# CargadorDeBaterias.net
KiCad netlist of a schematic drawn in Altium Designer
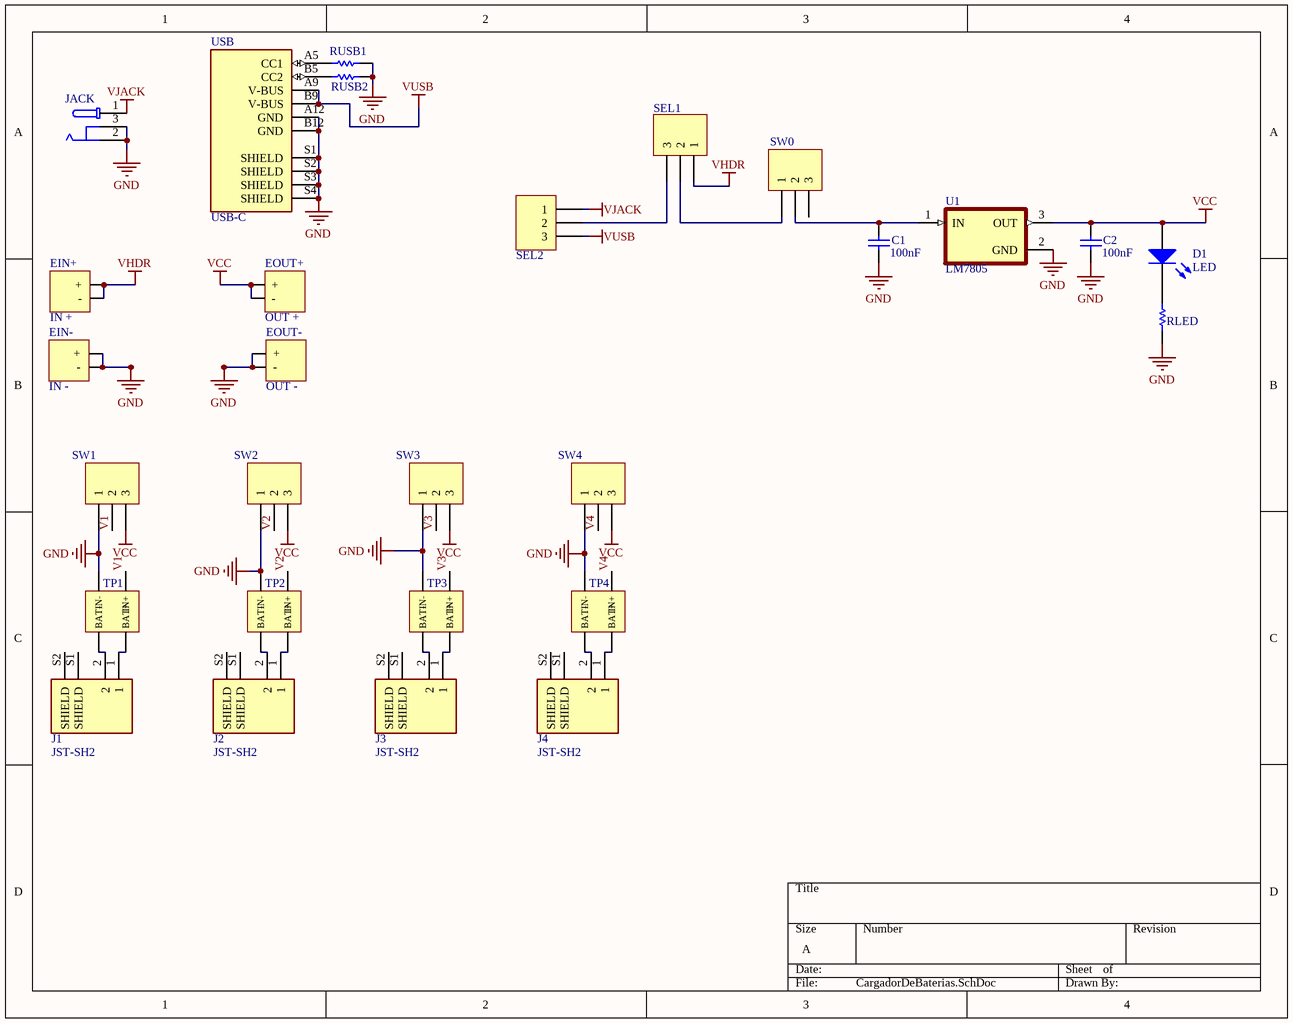
[diagram p0: CargadorDeBaterias.SchDoc]

(export (version "E")
  (design (tool "Eeschema 10.0.6"))
  (components
    (comp (ref "C1")
      (value "100nF")
      (footprint "CAP 0805")
      (description "Capacitor")
      (fields (field (name "Comment") "0805 100nF Capacitor") (field (name "PUBLISHER") "Altium Limited"))
      (libsource (lib "CargadorDeBaterias") (part "Cap"))
    )
    (comp (ref "C2")
      (value "100nF")
      (footprint "CAP 0805")
      (description "Capacitor")
      (fields (field (name "Comment") "0805 100nF Capacitor") (field (name "PUBLISHER") "Altium Limited"))
      (libsource (lib "CargadorDeBaterias") (part "Cap"))
    )
    (comp (ref "D1")
      (value "LED")
      (footprint "LED")
      (fields (field (name "PUBLISHER") "Altium Limited"))
      (libsource (lib "CargadorDeBaterias") (part "LED"))
    )
    (comp (ref "EIN+")
      (value "IN +")
      (footprint "HEADER x2")
      (fields (field (name "PUBLISHER") "Altium Limited"))
      (libsource (lib "") (part "HEADER X2_1"))
    )
    (comp (ref "EIN-")
      (value "IN -")
      (footprint "HEADER x2")
      (fields (field (name "PUBLISHER") "Altium Limited"))
      (libsource (lib "") (part "HEADER X2_1"))
    )
    (comp (ref "EOUT+")
      (value "OUT +")
      (footprint "HEADER x2")
      (fields (field (name "PUBLISHER") "Altium Limited"))
      (libsource (lib "CargadorDeBaterias") (part "HEADER X2"))
    )
    (comp (ref "EOUT-")
      (value "OUT -")
      (footprint "HEADER x2")
      (fields (field (name "PUBLISHER") "Altium Limited"))
      (libsource (lib "CargadorDeBaterias") (part "HEADER X2"))
    )
    (comp (ref "J1")
      (value "JST-SH2")
      (footprint "JST-SH2")
      (fields (field (name "MP") "BM02B-SRSS-TB(LF)(SN)"))
      (libsource (lib "CargadorDeBaterias") (part "JST-SH2"))
    )
    (comp (ref "J2")
      (value "JST-SH2")
      (footprint "JST-SH2")
      (fields (field (name "MP") "BM02B-SRSS-TB(LF)(SN)"))
      (libsource (lib "CargadorDeBaterias") (part "JST-SH2"))
    )
    (comp (ref "J3")
      (value "JST-SH2")
      (footprint "JST-SH2")
      (fields (field (name "MP") "BM02B-SRSS-TB(LF)(SN)"))
      (libsource (lib "CargadorDeBaterias") (part "JST-SH2"))
    )
    (comp (ref "J4")
      (value "JST-SH2")
      (footprint "JST-SH2")
      (fields (field (name "MP") "BM02B-SRSS-TB(LF)(SN)"))
      (libsource (lib "CargadorDeBaterias") (part "JST-SH2"))
    )
    (comp (ref "JACK")
      (value "JACK 5MM")
      (footprint "JACK 5MM")
      (fields (field (name "MF") "MPD") (field (name "MP") "EJ508A"))
      (libsource (lib "CargadorDeBaterias") (part "JACK 5MM"))
    )
    (comp (ref "RLED")
      (value "220ohm 0805 resistor")
      (footprint "RES 0805")
      (fields (field (name "PUBLISHER") "Altium Limited"))
      (libsource (lib "CargadorDeBaterias") (part "RESISTOR 1/4W"))
    )
    (comp (ref "RUSB1")
      (value "5,1Kohm 0805 resistor")
      (footprint "RES 0805")
      (fields (field (name "PUBLISHER") "Altium Limited"))
      (libsource (lib "CargadorDeBaterias") (part "RESISTOR 1/4W"))
    )
    (comp (ref "RUSB2")
      (value "5,1Kohm 0805 resistor")
      (footprint "RES 0805")
      (fields (field (name "PUBLISHER") "Altium Limited"))
      (libsource (lib "CargadorDeBaterias") (part "RESISTOR 1/4W"))
    )
    (comp (ref "SEL1")
      (value "~")
      (footprint "SWITCH PALANCA")
      (fields (field (name "PUBLISHER") "Altium Limited"))
      (libsource (lib "") (part "SLIDE SWITCH_2"))
    )
    (comp (ref "SEL2")
      (value "~")
      (footprint "SWITCH PALANCA")
      (fields (field (name "PUBLISHER") "Altium Limited"))
      (libsource (lib "") (part "SLIDE SWITCH_1"))
    )
    (comp (ref "SW0")
      (value "SLIDE SWITCH")
      (footprint "SWITCH PALANCA")
      (fields (field (name "PUBLISHER") "Altium Limited"))
      (libsource (lib "CargadorDeBaterias") (part "SLIDE SWITCH"))
    )
    (comp (ref "SW1")
      (value "~")
      (footprint "SWITCH PALANCA")
      (fields (field (name "PUBLISHER") "Altium Limited"))
      (libsource (lib "librerias (2)") (part "SLIDE SWITCH"))
    )
    (comp (ref "SW2")
      (value "~")
      (footprint "SWITCH PALANCA")
      (fields (field (name "PUBLISHER") "Altium Limited"))
      (libsource (lib "librerias (2)") (part "SLIDE SWITCH"))
    )
    (comp (ref "SW3")
      (value "~")
      (footprint "SWITCH PALANCA")
      (fields (field (name "PUBLISHER") "Altium Limited"))
      (libsource (lib "librerias (2)") (part "SLIDE SWITCH"))
    )
    (comp (ref "SW4")
      (value "~")
      (footprint "SWITCH PALANCA")
      (fields (field (name "PUBLISHER") "Altium Limited"))
      (libsource (lib "librerias (2)") (part "SLIDE SWITCH"))
    )
    (comp (ref "TP1")
      (value "TP 4056")
      (footprint "TP 4056")
      (libsource (lib "librerias (2)") (part "TP 4056"))
    )
    (comp (ref "TP2")
      (value "TP 4056")
      (footprint "TP 4056")
      (libsource (lib "librerias (2)") (part "TP 4056"))
    )
    (comp (ref "TP3")
      (value "TP 4056")
      (footprint "TP 4056")
      (libsource (lib "librerias (2)") (part "TP 4056"))
    )
    (comp (ref "TP4")
      (value "TP 4056")
      (footprint "TP 4056")
      (libsource (lib "librerias (2)") (part "TP 4056"))
    )
    (comp (ref "U1")
      (value "LM7805")
      (footprint "TO220")
      (fields (field (name "MF") "ON Semiconductor") (field (name "MP") "LM7805CT"))
      (libsource (lib "CargadorDeBaterias") (part "LM7805"))
    )
    (comp (ref "USB")
      (value "USB-C")
      (footprint "USB-C")
      (description "Type C, 3 A, Right Angle, Surface Mount (SMT), Power-Only USB Receptacle")
      (fields (field (name "MP") "UJC-HP-3-SMT-TR"))
      (libsource (lib "CargadorDeBaterias") (part "USB-C"))
    )
  )
  (nets
    (net (code "1") (name "/V1") (class "Default")
      (node (ref "SW1") (pin "2") (pinfunction "2_2") (pintype "passive"))
      (node (ref "TP1") (pin "0") (pinfunction "IN+_0") (pintype "passive"))
    )
    (net (code "2") (name "/V2") (class "Default")
      (node (ref "SW2") (pin "2") (pinfunction "2_2") (pintype "passive"))
      (node (ref "TP2") (pin "0") (pinfunction "IN+_0") (pintype "passive"))
    )
    (net (code "3") (name "/V3") (class "Default")
      (node (ref "SW3") (pin "2") (pinfunction "2_2") (pintype "passive"))
      (node (ref "TP3") (pin "0") (pinfunction "IN+_0") (pintype "passive"))
    )
    (net (code "4") (name "/V4") (class "Default")
      (node (ref "SW4") (pin "2") (pinfunction "2_2") (pintype "passive"))
      (node (ref "TP4") (pin "0") (pinfunction "IN+_0") (pintype "passive"))
    )
    (net (code "5") (name "GND") (class "Default")
      (node (ref "C1") (pin "1") (pinfunction "1_1") (pintype "passive"))
      (node (ref "C2") (pin "1") (pinfunction "1_1") (pintype "passive"))
      (node (ref "EIN-") (pin "+") (pinfunction "+_+") (pintype "passive"))
      (node (ref "EIN-") (pin "-") (pinfunction "-_-") (pintype "passive"))
      (node (ref "EOUT-") (pin "+") (pinfunction "+_+") (pintype "passive"))
      (node (ref "EOUT-") (pin "-") (pinfunction "-_-") (pintype "passive"))
      (node (ref "JACK") (pin "2") (pinfunction "GND_2") (pintype "passive"))
      (node (ref "JACK") (pin "3") (pinfunction "GND_3") (pintype "passive"))
      (node (ref "RLED") (pin "1") (pinfunction "1_1") (pintype "passive"))
      (node (ref "RUSB1") (pin "2") (pinfunction "2_2") (pintype "passive"))
      (node (ref "RUSB2") (pin "2") (pinfunction "2_2") (pintype "passive"))
      (node (ref "SW1") (pin "1") (pinfunction "1_1") (pintype "passive"))
      (node (ref "SW2") (pin "1") (pinfunction "1_1") (pintype "passive"))
      (node (ref "SW3") (pin "1") (pinfunction "1_1") (pintype "passive"))
      (node (ref "SW4") (pin "1") (pinfunction "1_1") (pintype "passive"))
      (node (ref "TP1") (pin "1") (pinfunction "IN-_1") (pintype "passive"))
      (node (ref "TP2") (pin "1") (pinfunction "IN-_1") (pintype "passive"))
      (node (ref "TP3") (pin "1") (pinfunction "IN-_1") (pintype "passive"))
      (node (ref "TP4") (pin "1") (pinfunction "IN-_1") (pintype "passive"))
      (node (ref "U1") (pin "2") (pinfunction "GND_2") (pintype "power_in"))
      (node (ref "USB") (pin "A12") (pinfunction "GND_A12") (pintype "power_in"))
      (node (ref "USB") (pin "B12") (pinfunction "GND_B12") (pintype "power_in"))
      (node (ref "USB") (pin "S1") (pinfunction "SHIELD_S1") (pintype "passive"))
      (node (ref "USB") (pin "S2") (pinfunction "SHIELD_S2") (pintype "passive"))
      (node (ref "USB") (pin "S3") (pinfunction "SHIELD_S3") (pintype "passive"))
      (node (ref "USB") (pin "S4") (pinfunction "SHIELD_S4") (pintype "passive"))
    )
    (net (code "6") (name "Net-(D1-K)") (class "Default")
      (node (ref "D1") (pin "1") (pinfunction "K_1") (pintype "passive"))
      (node (ref "RLED") (pin "2") (pinfunction "2_2") (pintype "passive"))
    )
    (net (code "7") (name "Net-(SEL1-Pad2)") (class "Default")
      (node (ref "SEL1") (pin "2") (pinfunction "2_2") (pintype "passive"))
      (node (ref "SW0") (pin "1") (pinfunction "1_1") (pintype "passive"))
    )
    (net (code "8") (name "Net-(SEL1-Pad3)") (class "Default")
      (node (ref "SEL1") (pin "3") (pinfunction "3_3") (pintype "passive"))
      (node (ref "SEL2") (pin "2") (pinfunction "2_2") (pintype "passive"))
    )
    (net (code "9") (name "Net-(TP1-BAT+)") (class "Default")
      (node (ref "J1") (pin "1") (pinfunction "1_1") (pintype "passive"))
      (node (ref "TP1") (pin "2") (pinfunction "BAT+_2") (pintype "passive"))
    )
    (net (code "10") (name "Net-(TP1-BAT-)") (class "Default")
      (node (ref "J1") (pin "2") (pinfunction "2_2") (pintype "passive"))
      (node (ref "TP1") (pin "3") (pinfunction "BAT-_3") (pintype "passive"))
    )
    (net (code "11") (name "Net-(TP2-BAT+)") (class "Default")
      (node (ref "J2") (pin "1") (pinfunction "1_1") (pintype "passive"))
      (node (ref "TP2") (pin "2") (pinfunction "BAT+_2") (pintype "passive"))
    )
    (net (code "12") (name "Net-(TP2-BAT-)") (class "Default")
      (node (ref "J2") (pin "2") (pinfunction "2_2") (pintype "passive"))
      (node (ref "TP2") (pin "3") (pinfunction "BAT-_3") (pintype "passive"))
    )
    (net (code "13") (name "Net-(TP3-BAT+)") (class "Default")
      (node (ref "J3") (pin "1") (pinfunction "1_1") (pintype "passive"))
      (node (ref "TP3") (pin "2") (pinfunction "BAT+_2") (pintype "passive"))
    )
    (net (code "14") (name "Net-(TP3-BAT-)") (class "Default")
      (node (ref "J3") (pin "2") (pinfunction "2_2") (pintype "passive"))
      (node (ref "TP3") (pin "3") (pinfunction "BAT-_3") (pintype "passive"))
    )
    (net (code "15") (name "Net-(TP4-BAT+)") (class "Default")
      (node (ref "J4") (pin "1") (pinfunction "1_1") (pintype "passive"))
      (node (ref "TP4") (pin "2") (pinfunction "BAT+_2") (pintype "passive"))
    )
    (net (code "16") (name "Net-(TP4-BAT-)") (class "Default")
      (node (ref "J4") (pin "2") (pinfunction "2_2") (pintype "passive"))
      (node (ref "TP4") (pin "3") (pinfunction "BAT-_3") (pintype "passive"))
    )
    (net (code "17") (name "Net-(U1-IN)") (class "Default")
      (node (ref "C1") (pin "2") (pinfunction "2_2") (pintype "passive"))
      (node (ref "SW0") (pin "2") (pinfunction "2_2") (pintype "passive"))
      (node (ref "U1") (pin "1") (pinfunction "IN_1") (pintype "input"))
    )
    (net (code "18") (name "Net-(USB-CC1)") (class "Default")
      (node (ref "RUSB1") (pin "1") (pinfunction "1_1") (pintype "passive"))
      (node (ref "USB") (pin "A5") (pinfunction "CC1_A5") (pintype "bidirectional"))
    )
    (net (code "19") (name "Net-(USB-CC2)") (class "Default")
      (node (ref "RUSB2") (pin "1") (pinfunction "1_1") (pintype "passive"))
      (node (ref "USB") (pin "B5") (pinfunction "CC2_B5") (pintype "bidirectional"))
    )
    (net (code "20") (name "VCC") (class "Default")
      (node (ref "C2") (pin "2") (pinfunction "2_2") (pintype "passive"))
      (node (ref "D1") (pin "0") (pinfunction "A_0") (pintype "passive"))
      (node (ref "EOUT+") (pin "+") (pinfunction "+_+") (pintype "passive"))
      (node (ref "EOUT+") (pin "-") (pinfunction "-_-") (pintype "passive"))
      (node (ref "SW1") (pin "3") (pinfunction "3_3") (pintype "passive"))
      (node (ref "SW2") (pin "3") (pinfunction "3_3") (pintype "passive"))
      (node (ref "SW3") (pin "3") (pinfunction "3_3") (pintype "passive"))
      (node (ref "SW4") (pin "3") (pinfunction "3_3") (pintype "passive"))
      (node (ref "U1") (pin "3") (pinfunction "OUT_3") (pintype "output"))
    )
    (net (code "21") (name "VHDR") (class "Default")
      (node (ref "EIN+") (pin "+") (pinfunction "+_+") (pintype "passive"))
      (node (ref "EIN+") (pin "-") (pinfunction "-_-") (pintype "passive"))
      (node (ref "SEL1") (pin "1") (pinfunction "1_1") (pintype "passive"))
    )
    (net (code "22") (name "VJACK") (class "Default")
      (node (ref "JACK") (pin "1") (pinfunction "VCC_1") (pintype "passive"))
      (node (ref "SEL2") (pin "1") (pinfunction "1_1") (pintype "passive"))
    )
    (net (code "23") (name "VUSB") (class "Default")
      (node (ref "SEL2") (pin "3") (pinfunction "3_3") (pintype "passive"))
      (node (ref "USB") (pin "A9") (pinfunction "V-BUS_A9") (pintype "power_in"))
      (node (ref "USB") (pin "B9") (pinfunction "V-BUS_B9") (pintype "power_in"))
    )
    (net (code "24") (name "unconnected-(J1-SHIELD-PadS1)") (class "Default")
      (node (ref "J1") (pin "S1") (pinfunction "SHIELD_S1") (pintype "passive"))
    )
    (net (code "25") (name "unconnected-(J1-SHIELD-PadS2)") (class "Default")
      (node (ref "J1") (pin "S2") (pinfunction "SHIELD_S2") (pintype "passive"))
    )
    (net (code "26") (name "unconnected-(J2-SHIELD-PadS1)") (class "Default")
      (node (ref "J2") (pin "S1") (pinfunction "SHIELD_S1") (pintype "passive"))
    )
    (net (code "27") (name "unconnected-(J2-SHIELD-PadS2)") (class "Default")
      (node (ref "J2") (pin "S2") (pinfunction "SHIELD_S2") (pintype "passive"))
    )
    (net (code "28") (name "unconnected-(J3-SHIELD-PadS1)") (class "Default")
      (node (ref "J3") (pin "S1") (pinfunction "SHIELD_S1") (pintype "passive"))
    )
    (net (code "29") (name "unconnected-(J3-SHIELD-PadS2)") (class "Default")
      (node (ref "J3") (pin "S2") (pinfunction "SHIELD_S2") (pintype "passive"))
    )
    (net (code "30") (name "unconnected-(J4-SHIELD-PadS1)") (class "Default")
      (node (ref "J4") (pin "S1") (pinfunction "SHIELD_S1") (pintype "passive"))
    )
    (net (code "31") (name "unconnected-(J4-SHIELD-PadS2)") (class "Default")
      (node (ref "J4") (pin "S2") (pinfunction "SHIELD_S2") (pintype "passive"))
    )
    (net (code "32") (name "unconnected-(SW0-Pad3)") (class "Default")
      (node (ref "SW0") (pin "3") (pinfunction "3_3") (pintype "passive"))
    )
  )
)
